# STM32.net
KiCad netlist of a schematic drawn in Altium Designer
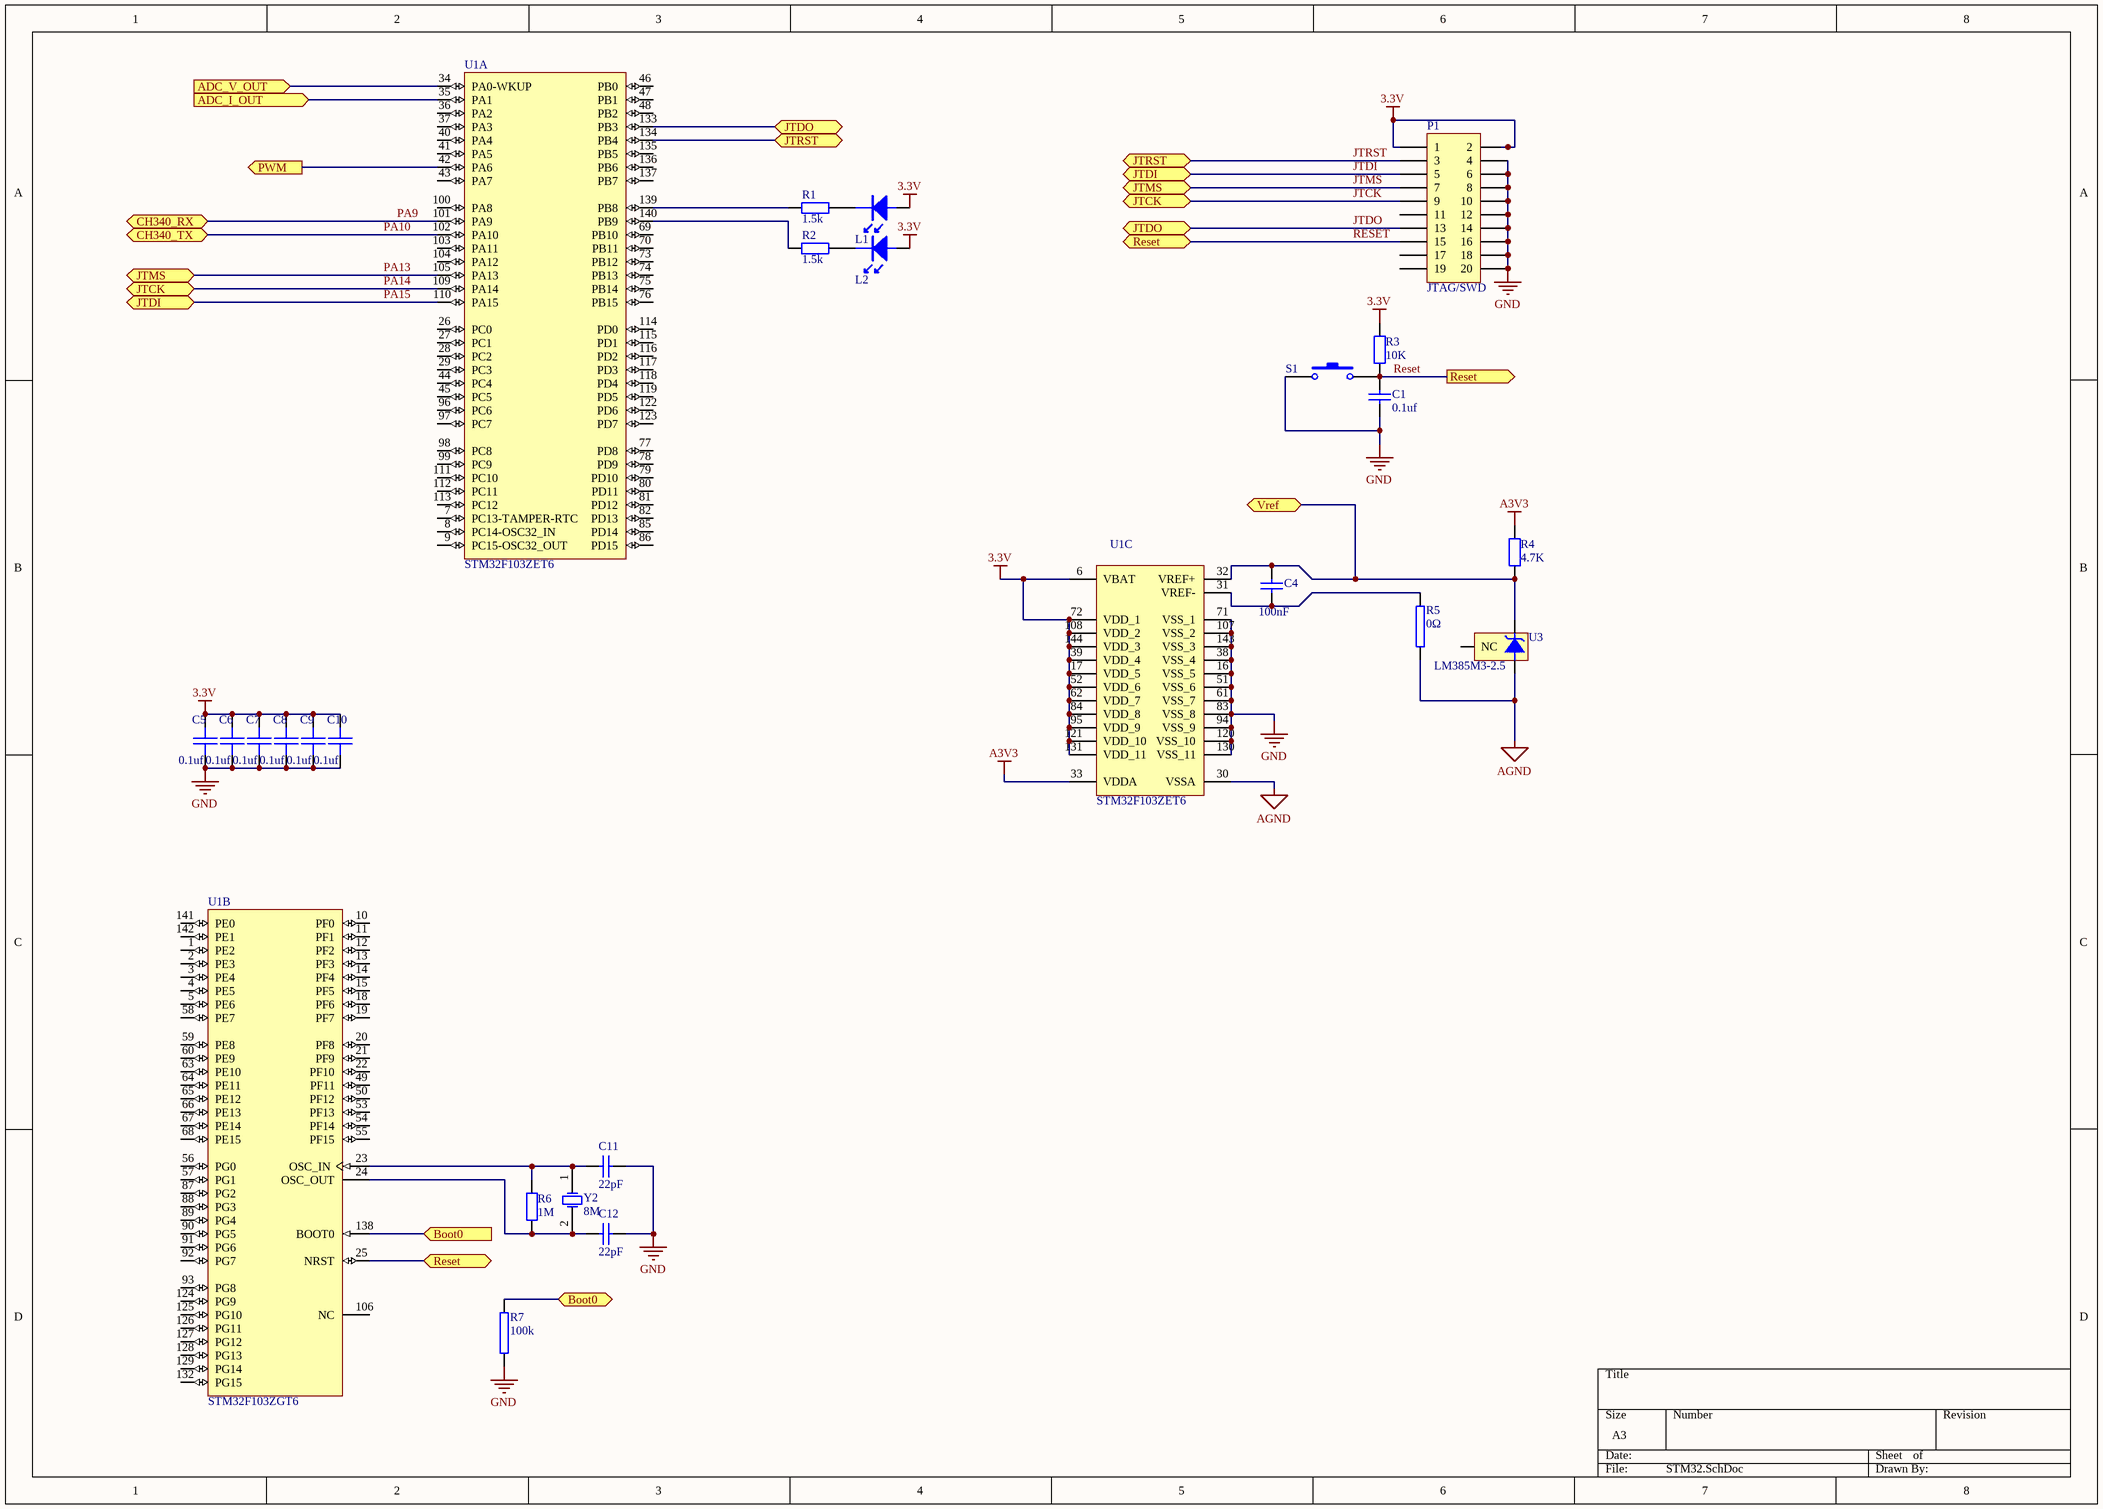
[diagram p0: STM32.SchDoc]

(export (version "E")
  (design (tool "Eeschema 10.0.6"))
  (components
    (comp (ref "C1")
      (value "0.1uf")
      (footprint "0805R")
      (description "Capacitor")
      (fields (field (name "PUBLISHER") "Altium Limited"))
      (libsource (lib "Miscellaneous Devices") (part "Cap"))
    )
    (comp (ref "C4")
      (value "100nF")
      (footprint "C-RAD-0805")
      (description "无极性电容")
      (fields (field (name "PUBLISHER") "Altium Limited"))
      (libsource (lib "Fszhang") (part "Cap"))
    )
    (comp (ref "C5")
      (value "0.1uf")
      (footprint "0805")
      (description "Capacitor")
      (libsource (lib "myIntegrated_Library1") (part "CAP1_1"))
    )
    (comp (ref "C6")
      (value "0.1uf")
      (footprint "0805")
      (description "Capacitor")
      (libsource (lib "myIntegrated_Library1") (part "CAP1_1"))
    )
    (comp (ref "C7")
      (value "0.1uf")
      (footprint "0805")
      (description "Capacitor")
      (libsource (lib "myIntegrated_Library1") (part "CAP1_1"))
    )
    (comp (ref "C8")
      (value "0.1uf")
      (footprint "0805")
      (description "Capacitor")
      (libsource (lib "myIntegrated_Library1") (part "CAP1_1"))
    )
    (comp (ref "C9")
      (value "0.1uf")
      (footprint "0805")
      (description "Capacitor")
      (libsource (lib "myIntegrated_Library1") (part "CAP1_1"))
    )
    (comp (ref "C10")
      (value "0.1uf")
      (footprint "0805")
      (description "Capacitor")
      (libsource (lib "myIntegrated_Library1") (part "CAP1_1"))
    )
    (comp (ref "C11")
      (value "22pF")
      (footprint "0805R")
      (description "Capacitor")
      (fields (field (name "PUBLISHER") "Altium Limited"))
      (libsource (lib "Miscellaneous Devices") (part "Cap"))
    )
    (comp (ref "C12")
      (value "22pF")
      (footprint "0805R")
      (description "Capacitor")
      (fields (field (name "PUBLISHER") "Altium Limited"))
      (libsource (lib "Miscellaneous Devices") (part "Cap"))
    )
    (comp (ref "L1")
      (value "POWER")
      (footprint "LED-0805")
      (libsource (lib "myIntegrated_Library1") (part "LED1"))
    )
    (comp (ref "L2")
      (value "POWER")
      (footprint "LED-0805")
      (libsource (lib "myIntegrated_Library1") (part "LED1"))
    )
    (comp (ref "P1")
      (value "JTAG/SWD")
      (footprint "JTAG_20")
      (description "Header, 10-Pin, Dual row")
      (fields (field (name "PUBLISHER") "Altium Limited"))
      (libsource (lib "Miscellaneous Connectors") (part "Header 10X2"))
    )
    (comp (ref "R1")
      (value "1.5k")
      (footprint "0805R")
      (description "Resistor")
      (fields (field (name "PUBLISHER") "Altium Limited"))
      (libsource (lib "Miscellaneous Devices") (part "Res2"))
    )
    (comp (ref "R2")
      (value "1.5k")
      (footprint "0805R")
      (description "Resistor")
      (fields (field (name "PUBLISHER") "Altium Limited"))
      (libsource (lib "Miscellaneous Devices") (part "Res2"))
    )
    (comp (ref "R3")
      (value "10K")
      (footprint "0805R")
      (description "Resistor")
      (fields (field (name "PUBLISHER") "Altium Limited"))
      (libsource (lib "") (part "Res2_1"))
    )
    (comp (ref "R4")
      (value "4.7K")
      (footprint "0805R")
      (description "Resistor")
      (fields (field (name "PUBLISHER") "Altium Limited"))
      (libsource (lib "") (part "Res2_1"))
    )
    (comp (ref "R5")
      (value "0Ω")
      (footprint "0805R")
      (libsource (lib "myIntegrated_Library1") (part "RES2_2"))
    )
    (comp (ref "R6")
      (value "1M")
      (footprint "0805R")
      (description "Resistor")
      (fields (field (name "PUBLISHER") "Altium Limited"))
      (libsource (lib "") (part "Res2_1"))
    )
    (comp (ref "R7")
      (value "100k")
      (footprint "0805R")
      (libsource (lib "myIntegrated_Library1") (part "RES2_2"))
    )
    (comp (ref "S1")
      (value "SW-PB")
      (footprint "SW_PB2_A1")
      (description "Switch")
      (fields (field (name "PUBLISHER") "Altium Limited"))
      (libsource (lib "Miscellaneous Devices") (part "SW-PB"))
    )
    (comp (ref "U1")
      (value "STM32F103ZET6")
      (footprint "STM-LQFP144_N")
      (fields (field (name "PARTNUMBER") "STM32F103ZET6"))
      (libsource (lib "STMicroelectronics STM32 F1") (part "STM32F103ZET6"))
    )
    (comp (ref "U3")
      (value "LM385M3-2.5")
      (footprint "MF03A_N")
      (description "Micropower Voltage Reference Diode, 3-pin SOT-23")
      (fields
        (field (name "MANUFACTURER") "National Semiconductor")
        (field (name "PUBLISHER") "Altium Limited")
      )
      (libsource (lib "NSC Voltage Reference") (part "LM385M3-2.5"))
    )
    (comp (ref "Y2")
      (value "8M")
      (footprint "晶振")
      (description "Crystal Oscillator")
      (fields (field (name "PUBLISHER") "Altium Limited"))
      (libsource (lib "Miscellaneous Devices") (part "XTAL"))
    )
  )
  (nets
    (net (code "1") (name "/ADC_I_OUT") (class "Default")
      (node (ref "U1") (pin "35") (pinfunction "PA1_35") (pintype "bidirectional"))
    )
    (net (code "2") (name "/ADC_V_OUT") (class "Default")
      (node (ref "U1") (pin "34") (pinfunction "PA0-WKUP_34") (pintype "bidirectional"))
    )
    (net (code "3") (name "/Boot0") (class "Default")
      (node (ref "R7") (pin "2") (pinfunction "2_2") (pintype "passive"))
      (node (ref "U1") (pin "138") (pinfunction "BOOT0_138") (pintype "input"))
    )
    (net (code "4") (name "/JTCK") (class "Default")
      (node (ref "P1") (pin "9") (pinfunction "9_9") (pintype "passive"))
      (node (ref "U1") (pin "109") (pinfunction "PA14_109") (pintype "bidirectional"))
    )
    (net (code "5") (name "/JTDI") (class "Default")
      (node (ref "P1") (pin "5") (pinfunction "5_5") (pintype "passive"))
      (node (ref "U1") (pin "110") (pinfunction "PA15_110") (pintype "bidirectional"))
    )
    (net (code "6") (name "/JTDO") (class "Default")
      (node (ref "P1") (pin "13") (pinfunction "13_13") (pintype "passive"))
      (node (ref "U1") (pin "133") (pinfunction "PB3_133") (pintype "bidirectional"))
    )
    (net (code "7") (name "/JTMS") (class "Default")
      (node (ref "P1") (pin "7") (pinfunction "7_7") (pintype "passive"))
      (node (ref "U1") (pin "105") (pinfunction "PA13_105") (pintype "bidirectional"))
    )
    (net (code "8") (name "/JTRST") (class "Default")
      (node (ref "P1") (pin "3") (pinfunction "3_3") (pintype "passive"))
      (node (ref "U1") (pin "134") (pinfunction "PB4_134") (pintype "bidirectional"))
    )
    (net (code "9") (name "/PA9") (class "Default")
      (node (ref "U1") (pin "101") (pinfunction "PA9_101") (pintype "bidirectional"))
    )
    (net (code "10") (name "/PA10") (class "Default")
      (node (ref "U1") (pin "102") (pinfunction "PA10_102") (pintype "bidirectional"))
    )
    (net (code "11") (name "/PWM") (class "Default")
      (node (ref "U1") (pin "42") (pinfunction "PA6_42") (pintype "bidirectional"))
    )
    (net (code "12") (name "/RESET") (class "Default")
      (node (ref "C1") (pin "2") (pinfunction "2_2") (pintype "passive"))
      (node (ref "P1") (pin "15") (pinfunction "15_15") (pintype "passive"))
      (node (ref "R3") (pin "2") (pinfunction "2_2") (pintype "passive"))
      (node (ref "S1") (pin "2") (pinfunction "2_2") (pintype "passive"))
      (node (ref "U1") (pin "25") (pinfunction "NRST_25") (pintype "bidirectional"))
    )
    (net (code "13") (name "/Vref") (class "Default")
      (node (ref "C4") (pin "2") (pinfunction "2_2") (pintype "passive"))
      (node (ref "R4") (pin "2") (pinfunction "2_2") (pintype "passive"))
      (node (ref "U1") (pin "32") (pinfunction "VREF+_32") (pintype "power_in"))
      (node (ref "U3") (pin "1") (pinfunction "+V_1") (pintype "passive"))
    )
    (net (code "14") (name "3.3V") (class "Default")
      (node (ref "C10") (pin "2") (pinfunction "2_2") (pintype "passive"))
      (node (ref "C5") (pin "2") (pinfunction "2_2") (pintype "passive"))
      (node (ref "C6") (pin "2") (pinfunction "2_2") (pintype "passive"))
      (node (ref "C7") (pin "2") (pinfunction "2_2") (pintype "passive"))
      (node (ref "C8") (pin "2") (pinfunction "2_2") (pintype "passive"))
      (node (ref "C9") (pin "2") (pinfunction "2_2") (pintype "passive"))
      (node (ref "L1") (pin "1") (pinfunction "1_1") (pintype "passive"))
      (node (ref "L2") (pin "1") (pinfunction "1_1") (pintype "passive"))
      (node (ref "P1") (pin "1") (pinfunction "1_1") (pintype "passive"))
      (node (ref "P1") (pin "2") (pinfunction "2_2") (pintype "passive"))
      (node (ref "R3") (pin "1") (pinfunction "1_1") (pintype "passive"))
      (node (ref "U1") (pin "108") (pinfunction "VDD_2_108") (pintype "power_in"))
      (node (ref "U1") (pin "121") (pinfunction "VDD_10_121") (pintype "power_in"))
      (node (ref "U1") (pin "131") (pinfunction "VDD_11_131") (pintype "power_in"))
      (node (ref "U1") (pin "144") (pinfunction "VDD_3_144") (pintype "power_in"))
      (node (ref "U1") (pin "17") (pinfunction "VDD_5_17") (pintype "power_in"))
      (node (ref "U1") (pin "39") (pinfunction "VDD_4_39") (pintype "power_in"))
      (node (ref "U1") (pin "52") (pinfunction "VDD_6_52") (pintype "power_in"))
      (node (ref "U1") (pin "6") (pinfunction "VBAT_6") (pintype "power_in"))
      (node (ref "U1") (pin "62") (pinfunction "VDD_7_62") (pintype "power_in"))
      (node (ref "U1") (pin "72") (pinfunction "VDD_1_72") (pintype "power_in"))
      (node (ref "U1") (pin "84") (pinfunction "VDD_8_84") (pintype "power_in"))
      (node (ref "U1") (pin "95") (pinfunction "VDD_9_95") (pintype "power_in"))
    )
    (net (code "15") (name "A3V3") (class "Default")
      (node (ref "R4") (pin "1") (pinfunction "1_1") (pintype "passive"))
      (node (ref "U1") (pin "33") (pinfunction "VDDA_33") (pintype "power_in"))
    )
    (net (code "16") (name "AGND") (class "Default")
      (node (ref "R5") (pin "1") (pinfunction "1_1") (pintype "passive"))
      (node (ref "U1") (pin "30") (pinfunction "VSSA_30") (pintype "power_in"))
      (node (ref "U3") (pin "2") (pinfunction "-V_2") (pintype "passive"))
    )
    (net (code "17") (name "GND") (class "Default")
      (node (ref "C1") (pin "1") (pinfunction "1_1") (pintype "passive"))
      (node (ref "C10") (pin "1") (pinfunction "1_1") (pintype "passive"))
      (node (ref "C11") (pin "1") (pinfunction "1_1") (pintype "passive"))
      (node (ref "C12") (pin "1") (pinfunction "1_1") (pintype "passive"))
      (node (ref "C5") (pin "1") (pinfunction "1_1") (pintype "passive"))
      (node (ref "C6") (pin "1") (pinfunction "1_1") (pintype "passive"))
      (node (ref "C7") (pin "1") (pinfunction "1_1") (pintype "passive"))
      (node (ref "C8") (pin "1") (pinfunction "1_1") (pintype "passive"))
      (node (ref "C9") (pin "1") (pinfunction "1_1") (pintype "passive"))
      (node (ref "P1") (pin "10") (pinfunction "10_10") (pintype "passive"))
      (node (ref "P1") (pin "12") (pinfunction "12_12") (pintype "passive"))
      (node (ref "P1") (pin "14") (pinfunction "14_14") (pintype "passive"))
      (node (ref "P1") (pin "16") (pinfunction "16_16") (pintype "passive"))
      (node (ref "P1") (pin "18") (pinfunction "18_18") (pintype "passive"))
      (node (ref "P1") (pin "20") (pinfunction "20_20") (pintype "passive"))
      (node (ref "P1") (pin "4") (pinfunction "4_4") (pintype "passive"))
      (node (ref "P1") (pin "6") (pinfunction "6_6") (pintype "passive"))
      (node (ref "P1") (pin "8") (pinfunction "8_8") (pintype "passive"))
      (node (ref "R7") (pin "1") (pinfunction "1_1") (pintype "passive"))
      (node (ref "S1") (pin "1") (pinfunction "1_1") (pintype "passive"))
      (node (ref "U1") (pin "107") (pinfunction "VSS_2_107") (pintype "power_in"))
      (node (ref "U1") (pin "120") (pinfunction "VSS_10_120") (pintype "power_in"))
      (node (ref "U1") (pin "130") (pinfunction "VSS_11_130") (pintype "power_in"))
      (node (ref "U1") (pin "143") (pinfunction "VSS_3_143") (pintype "power_in"))
      (node (ref "U1") (pin "16") (pinfunction "VSS_5_16") (pintype "power_in"))
      (node (ref "U1") (pin "38") (pinfunction "VSS_4_38") (pintype "power_in"))
      (node (ref "U1") (pin "51") (pinfunction "VSS_6_51") (pintype "power_in"))
      (node (ref "U1") (pin "61") (pinfunction "VSS_7_61") (pintype "power_in"))
      (node (ref "U1") (pin "71") (pinfunction "VSS_1_71") (pintype "power_in"))
      (node (ref "U1") (pin "83") (pinfunction "VSS_8_83") (pintype "power_in"))
      (node (ref "U1") (pin "94") (pinfunction "VSS_9_94") (pintype "power_in"))
    )
    (net (code "18") (name "Net-(L1-Pad2)") (class "Default")
      (node (ref "L1") (pin "2") (pinfunction "2_2") (pintype "passive"))
      (node (ref "R1") (pin "2") (pinfunction "2_2") (pintype "passive"))
    )
    (net (code "19") (name "Net-(L2-Pad2)") (class "Default")
      (node (ref "L2") (pin "2") (pinfunction "2_2") (pintype "passive"))
      (node (ref "R2") (pin "2") (pinfunction "2_2") (pintype "passive"))
    )
    (net (code "20") (name "Net-(U1A-PB8)") (class "Default")
      (node (ref "R1") (pin "1") (pinfunction "1_1") (pintype "passive"))
      (node (ref "U1") (pin "139") (pinfunction "PB8_139") (pintype "bidirectional"))
    )
    (net (code "21") (name "Net-(U1A-PB9)") (class "Default")
      (node (ref "R2") (pin "1") (pinfunction "1_1") (pintype "passive"))
      (node (ref "U1") (pin "140") (pinfunction "PB9_140") (pintype "bidirectional"))
    )
    (net (code "22") (name "Net-(U1B-OSC_IN)") (class "Default")
      (node (ref "C11") (pin "2") (pinfunction "2_2") (pintype "passive"))
      (node (ref "R6") (pin "1") (pinfunction "1_1") (pintype "passive"))
      (node (ref "U1") (pin "23") (pinfunction "OSC_IN_23") (pintype "input"))
      (node (ref "Y2") (pin "1") (pinfunction "OSC1_1") (pintype "passive"))
    )
    (net (code "23") (name "Net-(U1B-OSC_OUT)") (class "Default")
      (node (ref "C12") (pin "2") (pinfunction "2_2") (pintype "passive"))
      (node (ref "R6") (pin "2") (pinfunction "2_2") (pintype "passive"))
      (node (ref "U1") (pin "24") (pinfunction "OSC_OUT_24") (pintype "passive"))
      (node (ref "Y2") (pin "2") (pinfunction "OSC2_2") (pintype "passive"))
    )
    (net (code "24") (name "Net-(U1C-VREF-)") (class "Default")
      (node (ref "C4") (pin "1") (pinfunction "1_1") (pintype "passive"))
      (node (ref "R5") (pin "2") (pinfunction "2_2") (pintype "passive"))
      (node (ref "U1") (pin "31") (pinfunction "VREF-_31") (pintype "power_in"))
    )
    (net (code "25") (name "unconnected-(P1-Pad11)") (class "Default")
      (node (ref "P1") (pin "11") (pinfunction "11_11") (pintype "passive"))
    )
    (net (code "26") (name "unconnected-(P1-Pad17)") (class "Default")
      (node (ref "P1") (pin "17") (pinfunction "17_17") (pintype "passive"))
    )
    (net (code "27") (name "unconnected-(P1-Pad19)") (class "Default")
      (node (ref "P1") (pin "19") (pinfunction "19_19") (pintype "passive"))
    )
    (net (code "28") (name "unconnected-(U1A-PA2-Pad36)") (class "Default")
      (node (ref "U1") (pin "36") (pinfunction "PA2_36") (pintype "bidirectional"))
    )
    (net (code "29") (name "unconnected-(U1A-PA3-Pad37)") (class "Default")
      (node (ref "U1") (pin "37") (pinfunction "PA3_37") (pintype "bidirectional"))
    )
    (net (code "30") (name "unconnected-(U1A-PA4-Pad40)") (class "Default")
      (node (ref "U1") (pin "40") (pinfunction "PA4_40") (pintype "bidirectional"))
    )
    (net (code "31") (name "unconnected-(U1A-PA5-Pad41)") (class "Default")
      (node (ref "U1") (pin "41") (pinfunction "PA5_41") (pintype "bidirectional"))
    )
    (net (code "32") (name "unconnected-(U1A-PA7-Pad43)") (class "Default")
      (node (ref "U1") (pin "43") (pinfunction "PA7_43") (pintype "bidirectional"))
    )
    (net (code "33") (name "unconnected-(U1A-PA8-Pad100)") (class "Default")
      (node (ref "U1") (pin "100") (pinfunction "PA8_100") (pintype "bidirectional"))
    )
    (net (code "34") (name "unconnected-(U1A-PA11-Pad103)") (class "Default")
      (node (ref "U1") (pin "103") (pinfunction "PA11_103") (pintype "bidirectional"))
    )
    (net (code "35") (name "unconnected-(U1A-PA12-Pad104)") (class "Default")
      (node (ref "U1") (pin "104") (pinfunction "PA12_104") (pintype "bidirectional"))
    )
    (net (code "36") (name "unconnected-(U1A-PB0-Pad46)") (class "Default")
      (node (ref "U1") (pin "46") (pinfunction "PB0_46") (pintype "bidirectional"))
    )
    (net (code "37") (name "unconnected-(U1A-PB1-Pad47)") (class "Default")
      (node (ref "U1") (pin "47") (pinfunction "PB1_47") (pintype "bidirectional"))
    )
    (net (code "38") (name "unconnected-(U1A-PB2-Pad48)") (class "Default")
      (node (ref "U1") (pin "48") (pinfunction "PB2_48") (pintype "bidirectional"))
    )
    (net (code "39") (name "unconnected-(U1A-PB5-Pad135)") (class "Default")
      (node (ref "U1") (pin "135") (pinfunction "PB5_135") (pintype "bidirectional"))
    )
    (net (code "40") (name "unconnected-(U1A-PB6-Pad136)") (class "Default")
      (node (ref "U1") (pin "136") (pinfunction "PB6_136") (pintype "bidirectional"))
    )
    (net (code "41") (name "unconnected-(U1A-PB7-Pad137)") (class "Default")
      (node (ref "U1") (pin "137") (pinfunction "PB7_137") (pintype "bidirectional"))
    )
    (net (code "42") (name "unconnected-(U1A-PB10-Pad69)") (class "Default")
      (node (ref "U1") (pin "69") (pinfunction "PB10_69") (pintype "bidirectional"))
    )
    (net (code "43") (name "unconnected-(U1A-PB11-Pad70)") (class "Default")
      (node (ref "U1") (pin "70") (pinfunction "PB11_70") (pintype "bidirectional"))
    )
    (net (code "44") (name "unconnected-(U1A-PB12-Pad73)") (class "Default")
      (node (ref "U1") (pin "73") (pinfunction "PB12_73") (pintype "bidirectional"))
    )
    (net (code "45") (name "unconnected-(U1A-PB13-Pad74)") (class "Default")
      (node (ref "U1") (pin "74") (pinfunction "PB13_74") (pintype "bidirectional"))
    )
    (net (code "46") (name "unconnected-(U1A-PB14-Pad75)") (class "Default")
      (node (ref "U1") (pin "75") (pinfunction "PB14_75") (pintype "bidirectional"))
    )
    (net (code "47") (name "unconnected-(U1A-PB15-Pad76)") (class "Default")
      (node (ref "U1") (pin "76") (pinfunction "PB15_76") (pintype "bidirectional"))
    )
    (net (code "48") (name "unconnected-(U1A-PC0-Pad26)") (class "Default")
      (node (ref "U1") (pin "26") (pinfunction "PC0_26") (pintype "bidirectional"))
    )
    (net (code "49") (name "unconnected-(U1A-PC1-Pad27)") (class "Default")
      (node (ref "U1") (pin "27") (pinfunction "PC1_27") (pintype "bidirectional"))
    )
    (net (code "50") (name "unconnected-(U1A-PC2-Pad28)") (class "Default")
      (node (ref "U1") (pin "28") (pinfunction "PC2_28") (pintype "bidirectional"))
    )
    (net (code "51") (name "unconnected-(U1A-PC3-Pad29)") (class "Default")
      (node (ref "U1") (pin "29") (pinfunction "PC3_29") (pintype "bidirectional"))
    )
    (net (code "52") (name "unconnected-(U1A-PC4-Pad44)") (class "Default")
      (node (ref "U1") (pin "44") (pinfunction "PC4_44") (pintype "bidirectional"))
    )
    (net (code "53") (name "unconnected-(U1A-PC5-Pad45)") (class "Default")
      (node (ref "U1") (pin "45") (pinfunction "PC5_45") (pintype "bidirectional"))
    )
    (net (code "54") (name "unconnected-(U1A-PC6-Pad96)") (class "Default")
      (node (ref "U1") (pin "96") (pinfunction "PC6_96") (pintype "bidirectional"))
    )
    (net (code "55") (name "unconnected-(U1A-PC7-Pad97)") (class "Default")
      (node (ref "U1") (pin "97") (pinfunction "PC7_97") (pintype "bidirectional"))
    )
    (net (code "56") (name "unconnected-(U1A-PC8-Pad98)") (class "Default")
      (node (ref "U1") (pin "98") (pinfunction "PC8_98") (pintype "bidirectional"))
    )
    (net (code "57") (name "unconnected-(U1A-PC9-Pad99)") (class "Default")
      (node (ref "U1") (pin "99") (pinfunction "PC9_99") (pintype "bidirectional"))
    )
    (net (code "58") (name "unconnected-(U1A-PC10-Pad111)") (class "Default")
      (node (ref "U1") (pin "111") (pinfunction "PC10_111") (pintype "bidirectional"))
    )
    (net (code "59") (name "unconnected-(U1A-PC11-Pad112)") (class "Default")
      (node (ref "U1") (pin "112") (pinfunction "PC11_112") (pintype "bidirectional"))
    )
    (net (code "60") (name "unconnected-(U1A-PC12-Pad113)") (class "Default")
      (node (ref "U1") (pin "113") (pinfunction "PC12_113") (pintype "bidirectional"))
    )
    (net (code "61") (name "unconnected-(U1A-PC13-TAMPER-RTC-Pad7)") (class "Default")
      (node (ref "U1") (pin "7") (pinfunction "PC13-TAMPER-RTC_7") (pintype "bidirectional"))
    )
    (net (code "62") (name "unconnected-(U1A-PC14-OSC32_IN-Pad8)") (class "Default")
      (node (ref "U1") (pin "8") (pinfunction "PC14-OSC32_IN_8") (pintype "bidirectional"))
    )
    (net (code "63") (name "unconnected-(U1A-PC15-OSC32_OUT-Pad9)") (class "Default")
      (node (ref "U1") (pin "9") (pinfunction "PC15-OSC32_OUT_9") (pintype "bidirectional"))
    )
    (net (code "64") (name "unconnected-(U1A-PD0-Pad114)") (class "Default")
      (node (ref "U1") (pin "114") (pinfunction "PD0_114") (pintype "bidirectional"))
    )
    (net (code "65") (name "unconnected-(U1A-PD1-Pad115)") (class "Default")
      (node (ref "U1") (pin "115") (pinfunction "PD1_115") (pintype "bidirectional"))
    )
    (net (code "66") (name "unconnected-(U1A-PD2-Pad116)") (class "Default")
      (node (ref "U1") (pin "116") (pinfunction "PD2_116") (pintype "bidirectional"))
    )
    (net (code "67") (name "unconnected-(U1A-PD3-Pad117)") (class "Default")
      (node (ref "U1") (pin "117") (pinfunction "PD3_117") (pintype "bidirectional"))
    )
    (net (code "68") (name "unconnected-(U1A-PD4-Pad118)") (class "Default")
      (node (ref "U1") (pin "118") (pinfunction "PD4_118") (pintype "bidirectional"))
    )
    (net (code "69") (name "unconnected-(U1A-PD5-Pad119)") (class "Default")
      (node (ref "U1") (pin "119") (pinfunction "PD5_119") (pintype "bidirectional"))
    )
    (net (code "70") (name "unconnected-(U1A-PD6-Pad122)") (class "Default")
      (node (ref "U1") (pin "122") (pinfunction "PD6_122") (pintype "bidirectional"))
    )
    (net (code "71") (name "unconnected-(U1A-PD7-Pad123)") (class "Default")
      (node (ref "U1") (pin "123") (pinfunction "PD7_123") (pintype "bidirectional"))
    )
    (net (code "72") (name "unconnected-(U1A-PD8-Pad77)") (class "Default")
      (node (ref "U1") (pin "77") (pinfunction "PD8_77") (pintype "bidirectional"))
    )
    (net (code "73") (name "unconnected-(U1A-PD9-Pad78)") (class "Default")
      (node (ref "U1") (pin "78") (pinfunction "PD9_78") (pintype "bidirectional"))
    )
    (net (code "74") (name "unconnected-(U1A-PD10-Pad79)") (class "Default")
      (node (ref "U1") (pin "79") (pinfunction "PD10_79") (pintype "bidirectional"))
    )
    (net (code "75") (name "unconnected-(U1A-PD11-Pad80)") (class "Default")
      (node (ref "U1") (pin "80") (pinfunction "PD11_80") (pintype "bidirectional"))
    )
    (net (code "76") (name "unconnected-(U1A-PD12-Pad81)") (class "Default")
      (node (ref "U1") (pin "81") (pinfunction "PD12_81") (pintype "bidirectional"))
    )
    (net (code "77") (name "unconnected-(U1A-PD13-Pad82)") (class "Default")
      (node (ref "U1") (pin "82") (pinfunction "PD13_82") (pintype "bidirectional"))
    )
    (net (code "78") (name "unconnected-(U1A-PD14-Pad85)") (class "Default")
      (node (ref "U1") (pin "85") (pinfunction "PD14_85") (pintype "bidirectional"))
    )
    (net (code "79") (name "unconnected-(U1A-PD15-Pad86)") (class "Default")
      (node (ref "U1") (pin "86") (pinfunction "PD15_86") (pintype "bidirectional"))
    )
    (net (code "80") (name "unconnected-(U1B-NC-Pad106)") (class "Default")
      (node (ref "U1") (pin "106") (pinfunction "NC_106") (pintype "passive"))
    )
    (net (code "81") (name "unconnected-(U1B-PE0-Pad141)") (class "Default")
      (node (ref "U1") (pin "141") (pinfunction "PE0_141") (pintype "bidirectional"))
    )
    (net (code "82") (name "unconnected-(U1B-PE1-Pad142)") (class "Default")
      (node (ref "U1") (pin "142") (pinfunction "PE1_142") (pintype "bidirectional"))
    )
    (net (code "83") (name "unconnected-(U1B-PE2-Pad1)") (class "Default")
      (node (ref "U1") (pin "1") (pinfunction "PE2_1") (pintype "bidirectional"))
    )
    (net (code "84") (name "unconnected-(U1B-PE3-Pad2)") (class "Default")
      (node (ref "U1") (pin "2") (pinfunction "PE3_2") (pintype "bidirectional"))
    )
    (net (code "85") (name "unconnected-(U1B-PE4-Pad3)") (class "Default")
      (node (ref "U1") (pin "3") (pinfunction "PE4_3") (pintype "bidirectional"))
    )
    (net (code "86") (name "unconnected-(U1B-PE5-Pad4)") (class "Default")
      (node (ref "U1") (pin "4") (pinfunction "PE5_4") (pintype "bidirectional"))
    )
    (net (code "87") (name "unconnected-(U1B-PE6-Pad5)") (class "Default")
      (node (ref "U1") (pin "5") (pinfunction "PE6_5") (pintype "bidirectional"))
    )
    (net (code "88") (name "unconnected-(U1B-PE7-Pad58)") (class "Default")
      (node (ref "U1") (pin "58") (pinfunction "PE7_58") (pintype "bidirectional"))
    )
    (net (code "89") (name "unconnected-(U1B-PE8-Pad59)") (class "Default")
      (node (ref "U1") (pin "59") (pinfunction "PE8_59") (pintype "bidirectional"))
    )
    (net (code "90") (name "unconnected-(U1B-PE9-Pad60)") (class "Default")
      (node (ref "U1") (pin "60") (pinfunction "PE9_60") (pintype "bidirectional"))
    )
    (net (code "91") (name "unconnected-(U1B-PE10-Pad63)") (class "Default")
      (node (ref "U1") (pin "63") (pinfunction "PE10_63") (pintype "bidirectional"))
    )
    (net (code "92") (name "unconnected-(U1B-PE11-Pad64)") (class "Default")
      (node (ref "U1") (pin "64") (pinfunction "PE11_64") (pintype "bidirectional"))
    )
    (net (code "93") (name "unconnected-(U1B-PE12-Pad65)") (class "Default")
      (node (ref "U1") (pin "65") (pinfunction "PE12_65") (pintype "bidirectional"))
    )
    (net (code "94") (name "unconnected-(U1B-PE13-Pad66)") (class "Default")
      (node (ref "U1") (pin "66") (pinfunction "PE13_66") (pintype "bidirectional"))
    )
    (net (code "95") (name "unconnected-(U1B-PE14-Pad67)") (class "Default")
      (node (ref "U1") (pin "67") (pinfunction "PE14_67") (pintype "bidirectional"))
    )
    (net (code "96") (name "unconnected-(U1B-PE15-Pad68)") (class "Default")
      (node (ref "U1") (pin "68") (pinfunction "PE15_68") (pintype "bidirectional"))
    )
    (net (code "97") (name "unconnected-(U1B-PF0-Pad10)") (class "Default")
      (node (ref "U1") (pin "10") (pinfunction "PF0_10") (pintype "bidirectional"))
    )
    (net (code "98") (name "unconnected-(U1B-PF1-Pad11)") (class "Default")
      (node (ref "U1") (pin "11") (pinfunction "PF1_11") (pintype "bidirectional"))
    )
    (net (code "99") (name "unconnected-(U1B-PF2-Pad12)") (class "Default")
      (node (ref "U1") (pin "12") (pinfunction "PF2_12") (pintype "bidirectional"))
    )
    (net (code "100") (name "unconnected-(U1B-PF3-Pad13)") (class "Default")
      (node (ref "U1") (pin "13") (pinfunction "PF3_13") (pintype "bidirectional"))
    )
    (net (code "101") (name "unconnected-(U1B-PF4-Pad14)") (class "Default")
      (node (ref "U1") (pin "14") (pinfunction "PF4_14") (pintype "bidirectional"))
    )
    (net (code "102") (name "unconnected-(U1B-PF5-Pad15)") (class "Default")
      (node (ref "U1") (pin "15") (pinfunction "PF5_15") (pintype "bidirectional"))
    )
    (net (code "103") (name "unconnected-(U1B-PF6-Pad18)") (class "Default")
      (node (ref "U1") (pin "18") (pinfunction "PF6_18") (pintype "bidirectional"))
    )
    (net (code "104") (name "unconnected-(U1B-PF7-Pad19)") (class "Default")
      (node (ref "U1") (pin "19") (pinfunction "PF7_19") (pintype "bidirectional"))
    )
    (net (code "105") (name "unconnected-(U1B-PF8-Pad20)") (class "Default")
      (node (ref "U1") (pin "20") (pinfunction "PF8_20") (pintype "bidirectional"))
    )
    (net (code "106") (name "unconnected-(U1B-PF9-Pad21)") (class "Default")
      (node (ref "U1") (pin "21") (pinfunction "PF9_21") (pintype "bidirectional"))
    )
    (net (code "107") (name "unconnected-(U1B-PF10-Pad22)") (class "Default")
      (node (ref "U1") (pin "22") (pinfunction "PF10_22") (pintype "bidirectional"))
    )
    (net (code "108") (name "unconnected-(U1B-PF11-Pad49)") (class "Default")
      (node (ref "U1") (pin "49") (pinfunction "PF11_49") (pintype "bidirectional"))
    )
    (net (code "109") (name "unconnected-(U1B-PF12-Pad50)") (class "Default")
      (node (ref "U1") (pin "50") (pinfunction "PF12_50") (pintype "bidirectional"))
    )
    (net (code "110") (name "unconnected-(U1B-PF13-Pad53)") (class "Default")
      (node (ref "U1") (pin "53") (pinfunction "PF13_53") (pintype "bidirectional"))
    )
    (net (code "111") (name "unconnected-(U1B-PF14-Pad54)") (class "Default")
      (node (ref "U1") (pin "54") (pinfunction "PF14_54") (pintype "bidirectional"))
    )
    (net (code "112") (name "unconnected-(U1B-PF15-Pad55)") (class "Default")
      (node (ref "U1") (pin "55") (pinfunction "PF15_55") (pintype "bidirectional"))
    )
    (net (code "113") (name "unconnected-(U1B-PG0-Pad56)") (class "Default")
      (node (ref "U1") (pin "56") (pinfunction "PG0_56") (pintype "bidirectional"))
    )
    (net (code "114") (name "unconnected-(U1B-PG1-Pad57)") (class "Default")
      (node (ref "U1") (pin "57") (pinfunction "PG1_57") (pintype "bidirectional"))
    )
    (net (code "115") (name "unconnected-(U1B-PG2-Pad87)") (class "Default")
      (node (ref "U1") (pin "87") (pinfunction "PG2_87") (pintype "bidirectional"))
    )
    (net (code "116") (name "unconnected-(U1B-PG3-Pad88)") (class "Default")
      (node (ref "U1") (pin "88") (pinfunction "PG3_88") (pintype "bidirectional"))
    )
    (net (code "117") (name "unconnected-(U1B-PG4-Pad89)") (class "Default")
      (node (ref "U1") (pin "89") (pinfunction "PG4_89") (pintype "bidirectional"))
    )
    (net (code "118") (name "unconnected-(U1B-PG5-Pad90)") (class "Default")
      (node (ref "U1") (pin "90") (pinfunction "PG5_90") (pintype "bidirectional"))
    )
    (net (code "119") (name "unconnected-(U1B-PG6-Pad91)") (class "Default")
      (node (ref "U1") (pin "91") (pinfunction "PG6_91") (pintype "bidirectional"))
    )
    (net (code "120") (name "unconnected-(U1B-PG7-Pad92)") (class "Default")
      (node (ref "U1") (pin "92") (pinfunction "PG7_92") (pintype "bidirectional"))
    )
    (net (code "121") (name "unconnected-(U1B-PG8-Pad93)") (class "Default")
      (node (ref "U1") (pin "93") (pinfunction "PG8_93") (pintype "bidirectional"))
    )
    (net (code "122") (name "unconnected-(U1B-PG9-Pad124)") (class "Default")
      (node (ref "U1") (pin "124") (pinfunction "PG9_124") (pintype "bidirectional"))
    )
    (net (code "123") (name "unconnected-(U1B-PG10-Pad125)") (class "Default")
      (node (ref "U1") (pin "125") (pinfunction "PG10_125") (pintype "bidirectional"))
    )
    (net (code "124") (name "unconnected-(U1B-PG11-Pad126)") (class "Default")
      (node (ref "U1") (pin "126") (pinfunction "PG11_126") (pintype "bidirectional"))
    )
    (net (code "125") (name "unconnected-(U1B-PG12-Pad127)") (class "Default")
      (node (ref "U1") (pin "127") (pinfunction "PG12_127") (pintype "bidirectional"))
    )
    (net (code "126") (name "unconnected-(U1B-PG13-Pad128)") (class "Default")
      (node (ref "U1") (pin "128") (pinfunction "PG13_128") (pintype "bidirectional"))
    )
    (net (code "127") (name "unconnected-(U1B-PG14-Pad129)") (class "Default")
      (node (ref "U1") (pin "129") (pinfunction "PG14_129") (pintype "bidirectional"))
    )
    (net (code "128") (name "unconnected-(U1B-PG15-Pad132)") (class "Default")
      (node (ref "U1") (pin "132") (pinfunction "PG15_132") (pintype "bidirectional"))
    )
    (net (code "129") (name "unconnected-(U3-NC-Pad3)") (class "Default")
      (node (ref "U3") (pin "3") (pinfunction "NC_3") (pintype "passive"))
    )
  )
)
